# Hall_Sensor_cct.net
KiCad netlist of a schematic drawn in Altium Designer
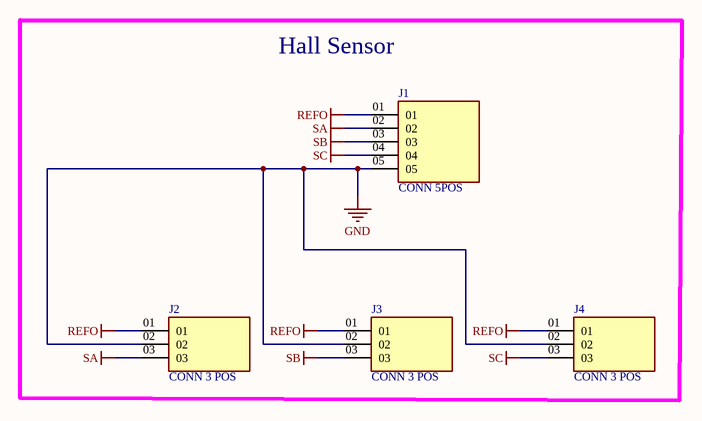
[diagram p0: Hall_Sensor_cct.SchDoc]

(export (version "E")
  (design (tool "Eeschema 10.0.6"))
  (components
    (comp (ref "J1")
      (value "CONN 5POS")
      (footprint "SAMTEC_SSQ-105-23-G-S")
      (description "CONN RCPT 5POS 0.1 GOLD PCB")
      (fields (field (name "MF") "Samtec") (field (name "MP") "SSQ-105-23-G-S"))
      (libsource (lib "PROJE") (part "CONN 5POS"))
    )
    (comp (ref "J2")
      (value "CONN 3 POS")
      (footprint "SAMTEC_SSQ-103-04-G-S")
      (description "CONN RCPT 3POS 0.1 GOLD PCB")
      (fields (field (name "MF") "Samtec") (field (name "MP") "SSQ-103-04-G-S"))
      (libsource (lib "PROJE") (part "CONN 3 POS"))
    )
    (comp (ref "J3")
      (value "CONN 3 POS")
      (footprint "SAMTEC_SSQ-103-04-G-S")
      (description "CONN RCPT 3POS 0.1 GOLD PCB")
      (fields (field (name "MF") "Samtec") (field (name "MP") "SSQ-103-04-G-S"))
      (libsource (lib "PROJE") (part "CONN 3 POS"))
    )
    (comp (ref "J4")
      (value "CONN 3 POS")
      (footprint "SAMTEC_SSQ-103-04-G-S")
      (description "CONN RCPT 3POS 0.1 GOLD PCB")
      (fields (field (name "MF") "Samtec") (field (name "MP") "SSQ-103-04-G-S"))
      (libsource (lib "PROJE") (part "CONN 3 POS"))
    )
  )
  (nets
    (net (code "1") (name "GND") (class "Default")
      (node (ref "J1") (pin "05") (pinfunction "05_05") (pintype "passive"))
      (node (ref "J2") (pin "02") (pinfunction "02_02") (pintype "passive"))
      (node (ref "J3") (pin "02") (pinfunction "02_02") (pintype "passive"))
      (node (ref "J4") (pin "02") (pinfunction "02_02") (pintype "passive"))
    )
    (net (code "2") (name "REFO") (class "Default")
      (node (ref "J1") (pin "01") (pinfunction "01_01") (pintype "passive"))
      (node (ref "J2") (pin "01") (pinfunction "01_01") (pintype "passive"))
      (node (ref "J3") (pin "01") (pinfunction "01_01") (pintype "passive"))
      (node (ref "J4") (pin "01") (pinfunction "01_01") (pintype "passive"))
    )
    (net (code "3") (name "SA") (class "Default")
      (node (ref "J1") (pin "02") (pinfunction "02_02") (pintype "passive"))
      (node (ref "J2") (pin "03") (pinfunction "03_03") (pintype "passive"))
    )
    (net (code "4") (name "SB") (class "Default")
      (node (ref "J1") (pin "03") (pinfunction "03_03") (pintype "passive"))
      (node (ref "J3") (pin "03") (pinfunction "03_03") (pintype "passive"))
    )
    (net (code "5") (name "SC") (class "Default")
      (node (ref "J1") (pin "04") (pinfunction "04_04") (pintype "passive"))
      (node (ref "J4") (pin "03") (pinfunction "03_03") (pintype "passive"))
    )
  )
)
